# ECG_PressureSensor.net
KiCad netlist of a schematic drawn in Altium Designer
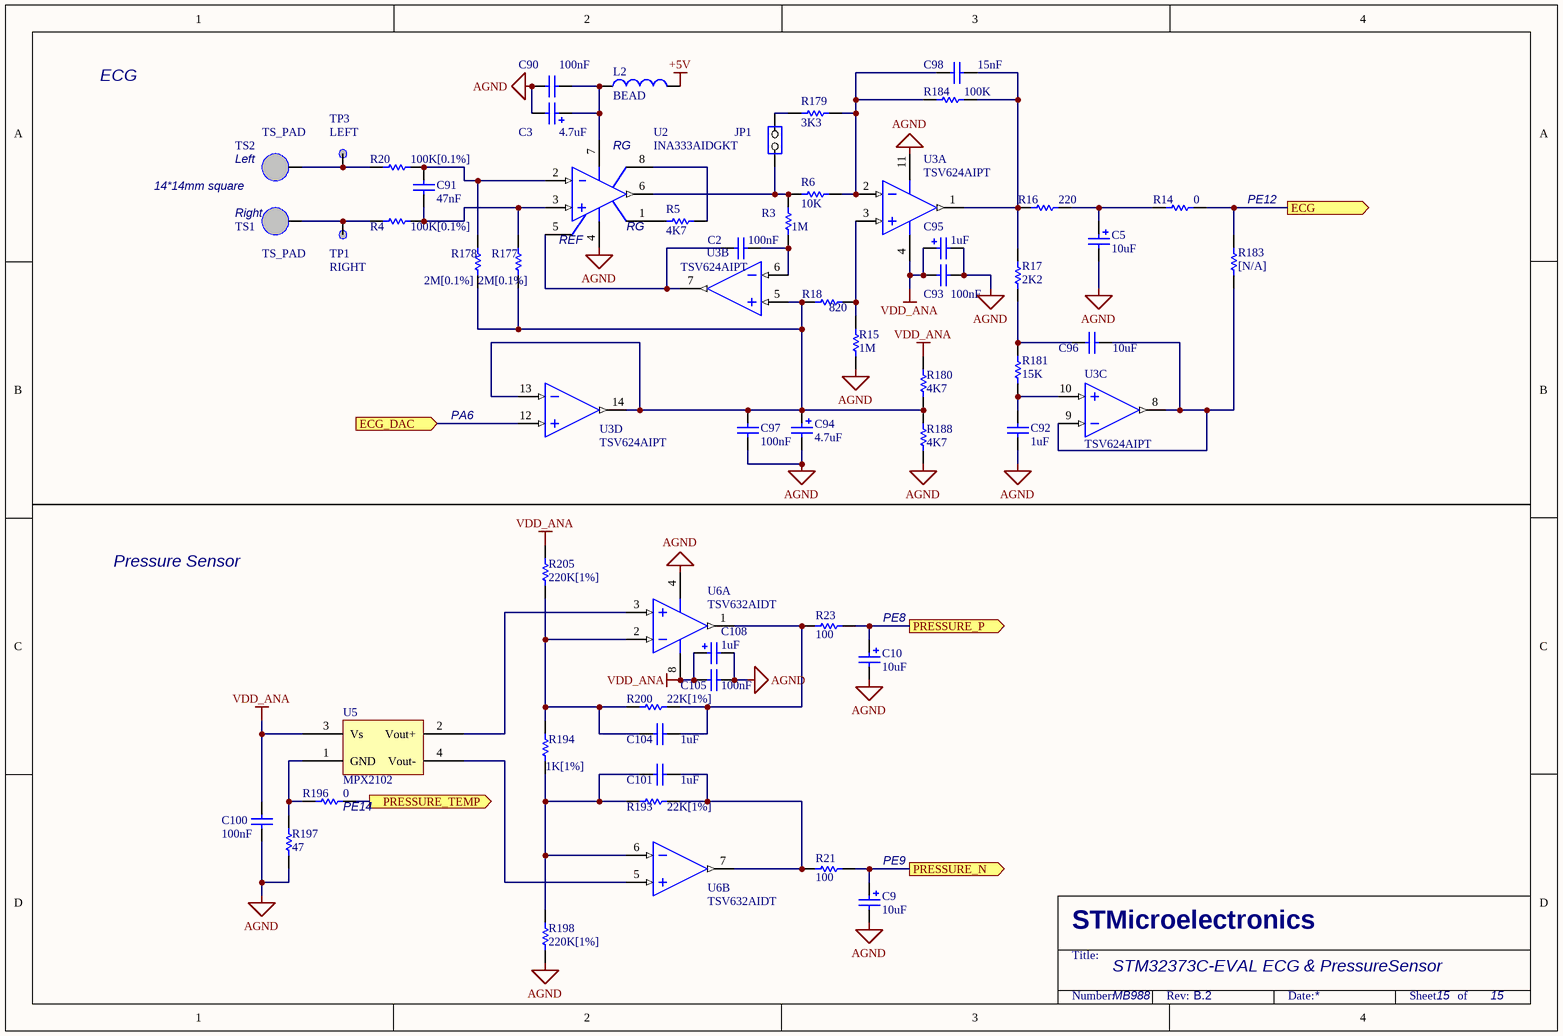
[diagram p0: ECG&PressureSensor.SchDoc]

(export (version "E")
  (design (tool "Eeschema 10.0.6"))
  (components
    (comp (ref "C2")
      (value "100nF")
      (footprint "0603C")
      (description "Capacitor")
      (fields (field (name "PUBLISHER") "Altium Limited"))
      (libsource (lib "Miscellaneous Devices") (part "CAP"))
    )
    (comp (ref "C3")
      (value "4.7uF")
      (footprint "TAN-A")
      (description "Polarized Capacitor (Radial)")
      (fields (field (name "PUBLISHER") "Altium Limited"))
      (libsource (lib "*") (part "Cap Pol1"))
    )
    (comp (ref "C5")
      (value "10uF")
      (footprint "TAN-A")
      (description "Polarized Capacitor (Radial)")
      (fields (field (name "PUBLISHER") "Altium Limited"))
      (libsource (lib "Miscellaneous Devices") (part "Cap Pol1"))
    )
    (comp (ref "C9")
      (value "10uF")
      (footprint "TAN-A")
      (description "Polarized Capacitor (Radial)")
      (fields (field (name "PUBLISHER") "Altium Limited"))
      (libsource (lib "Miscellaneous Devices") (part "Cap Pol1"))
    )
    (comp (ref "C10")
      (value "10uF")
      (footprint "TAN-A")
      (description "Polarized Capacitor (Radial)")
      (fields (field (name "PUBLISHER") "Altium Limited"))
      (libsource (lib "Miscellaneous Devices") (part "Cap Pol1"))
    )
    (comp (ref "C90")
      (value "100nF")
      (footprint "0603C")
      (description "Capacitor")
      (fields (field (name "PUBLISHER") "Altium Limited"))
      (libsource (lib "Miscellaneous Devices") (part "CAP"))
    )
    (comp (ref "C91")
      (value "47nF")
      (footprint "0603C")
      (description "Capacitor")
      (fields (field (name "PUBLISHER") "Altium Limited"))
      (libsource (lib "Miscellaneous Devices") (part "CAP"))
    )
    (comp (ref "C92")
      (value "1uF")
      (footprint "0603C")
      (description "Capacitor")
      (fields (field (name "PUBLISHER") "Altium Limited"))
      (libsource (lib "Miscellaneous Devices") (part "CAP"))
    )
    (comp (ref "C93")
      (value "100nF")
      (footprint "0603C")
      (description "Capacitor")
      (fields (field (name "PUBLISHER") "Altium Limited"))
      (libsource (lib "Miscellaneous Devices") (part "CAP"))
    )
    (comp (ref "C94")
      (value "4.7uF")
      (footprint "TAN-A")
      (description "Polarized Capacitor (Radial)")
      (fields (field (name "PUBLISHER") "Altium Limited"))
      (libsource (lib "*") (part "Cap Pol1"))
    )
    (comp (ref "C95")
      (value "1uF")
      (footprint "TAN-A")
      (description "Polarized Capacitor (Radial)")
      (fields (field (name "PUBLISHER") "Altium Limited"))
      (libsource (lib "Miscellaneous Devices") (part "Cap Pol1"))
    )
    (comp (ref "C96")
      (value "10uF")
      (footprint "0805C")
      (description "Capacitor")
      (fields (field (name "PUBLISHER") "Altium Limited"))
      (libsource (lib "Miscellaneous Devices") (part "CAP"))
    )
    (comp (ref "C97")
      (value "100nF")
      (footprint "0603C")
      (description "Capacitor")
      (fields (field (name "PUBLISHER") "Altium Limited"))
      (libsource (lib "Miscellaneous Devices") (part "CAP"))
    )
    (comp (ref "C98")
      (value "15nF")
      (footprint "0603C")
      (description "Capacitor")
      (fields (field (name "PUBLISHER") "Altium Limited"))
      (libsource (lib "Miscellaneous Devices") (part "CAP"))
    )
    (comp (ref "C100")
      (value "100nF")
      (footprint "0603C")
      (description "Capacitor")
      (fields (field (name "PUBLISHER") "Altium Limited"))
      (libsource (lib "Miscellaneous Devices") (part "CAP"))
    )
    (comp (ref "C101")
      (value "1uF")
      (footprint "0603C")
      (description "Capacitor")
      (fields (field (name "PUBLISHER") "Altium Limited"))
      (libsource (lib "Miscellaneous Devices") (part "CAP"))
    )
    (comp (ref "C104")
      (value "1uF")
      (footprint "0603C")
      (description "Capacitor")
      (fields (field (name "PUBLISHER") "Altium Limited"))
      (libsource (lib "Miscellaneous Devices") (part "CAP"))
    )
    (comp (ref "C105")
      (value "100nF")
      (footprint "0603C")
      (description "Capacitor")
      (fields (field (name "PUBLISHER") "Altium Limited"))
      (libsource (lib "Miscellaneous Devices") (part "CAP"))
    )
    (comp (ref "C108")
      (value "1uF")
      (footprint "TAN-A")
      (description "Polarized Capacitor (Radial)")
      (fields (field (name "PUBLISHER") "Altium Limited"))
      (libsource (lib "Miscellaneous Devices") (part "Cap Pol1"))
    )
    (comp (ref "JP1") (value "~") (footprint "SIP2") (libsource (lib "*") (part "JP2")))
    (comp (ref "L2")
      (value "BEAD")
      (footprint "0603L")
      (description "Inductor")
      (fields (field (name "PUBLISHER") "Altium Limited"))
      (libsource (lib "Miscellaneous Devices") (part "Inductor"))
    )
    (comp (ref "R3")
      (value "1M")
      (footprint "0603R")
      (description "Resistor")
      (fields (field (name "PUBLISHER") "Altium Limited"))
      (libsource (lib "Miscellaneous Devices") (part "Res1"))
    )
    (comp (ref "R4")
      (value "100K[0.1%]")
      (footprint "0603R")
      (description "Resistor")
      (fields (field (name "PUBLISHER") "Altium Limited"))
      (libsource (lib "Miscellaneous Devices") (part "Res1"))
    )
    (comp (ref "R5")
      (value "4K7")
      (footprint "0603R")
      (description "Resistor")
      (fields (field (name "PUBLISHER") "Altium Limited"))
      (libsource (lib "Miscellaneous Devices") (part "Res1"))
    )
    (comp (ref "R6")
      (value "10K")
      (footprint "0603R")
      (description "Resistor")
      (fields (field (name "PUBLISHER") "Altium Limited"))
      (libsource (lib "Miscellaneous Devices") (part "res1"))
    )
    (comp (ref "R14")
      (value "0")
      (footprint "0603R")
      (description "Resistor")
      (fields (field (name "PUBLISHER") "Altium Limited"))
      (libsource (lib "Miscellaneous Devices") (part "Res1"))
    )
    (comp (ref "R15")
      (value "1M")
      (footprint "0603R")
      (description "Resistor")
      (fields (field (name "PUBLISHER") "Altium Limited"))
      (libsource (lib "Miscellaneous Devices") (part "Res1"))
    )
    (comp (ref "R16")
      (value "220")
      (footprint "0603R")
      (description "Resistor")
      (fields (field (name "PUBLISHER") "Altium Limited"))
      (libsource (lib "Miscellaneous Devices") (part "Res1"))
    )
    (comp (ref "R17")
      (value "2K2")
      (description "Resistor")
      (fields (field (name "PUBLISHER") "Altium Limited"))
      (libsource (lib "Miscellaneous Devices") (part "Res1"))
    )
    (comp (ref "R18")
      (value "820")
      (footprint "0603R")
      (description "Resistor")
      (fields (field (name "PUBLISHER") "Altium Limited"))
      (libsource (lib "Miscellaneous Devices") (part "Res1"))
    )
    (comp (ref "R20")
      (value "100K[0.1%]")
      (footprint "0603R")
      (description "Resistor")
      (fields (field (name "PUBLISHER") "Altium Limited"))
      (libsource (lib "Miscellaneous Devices") (part "Res1"))
    )
    (comp (ref "R21")
      (value "100")
      (footprint "0603R")
      (description "Resistor")
      (fields (field (name "PUBLISHER") "Altium Limited"))
      (libsource (lib "Miscellaneous Devices") (part "Res1"))
    )
    (comp (ref "R23")
      (value "100")
      (footprint "0603R")
      (description "Resistor")
      (fields (field (name "PUBLISHER") "Altium Limited"))
      (libsource (lib "Miscellaneous Devices") (part "Res1"))
    )
    (comp (ref "R177")
      (value "2M[0.1%]")
      (footprint "0603R")
      (description "Resistor")
      (fields (field (name "PUBLISHER") "Altium Limited"))
      (libsource (lib "Miscellaneous Devices") (part "Res1"))
    )
    (comp (ref "R178")
      (value "2M[0.1%]")
      (footprint "0603R")
      (description "Resistor")
      (fields (field (name "PUBLISHER") "Altium Limited"))
      (libsource (lib "Miscellaneous Devices") (part "Res1"))
    )
    (comp (ref "R179")
      (value "3K3")
      (description "Resistor")
      (fields (field (name "PUBLISHER") "Altium Limited"))
      (libsource (lib "Miscellaneous Devices") (part "Res1"))
    )
    (comp (ref "R180")
      (value "4K7")
      (footprint "0603R")
      (description "Resistor")
      (fields (field (name "PUBLISHER") "Altium Limited"))
      (libsource (lib "Miscellaneous Devices") (part "Res1"))
    )
    (comp (ref "R181")
      (value "15K")
      (footprint "0603R")
      (description "Resistor")
      (fields (field (name "PUBLISHER") "Altium Limited"))
      (libsource (lib "Miscellaneous Devices") (part "Res1"))
    )
    (comp (ref "R183")
      (value "[N/A]")
      (footprint "0603R")
      (description "Resistor")
      (fields (field (name "PUBLISHER") "Altium Limited"))
      (libsource (lib "Miscellaneous Devices") (part "Res1"))
    )
    (comp (ref "R184")
      (value "100K")
      (footprint "0603R")
      (description "Resistor")
      (fields (field (name "PUBLISHER") "Altium Limited"))
      (libsource (lib "Miscellaneous Devices") (part "Res1"))
    )
    (comp (ref "R188")
      (value "4K7")
      (footprint "0603R")
      (description "Resistor")
      (fields (field (name "PUBLISHER") "Altium Limited"))
      (libsource (lib "Miscellaneous Devices") (part "Res1"))
    )
    (comp (ref "R193")
      (value "22K[1%]")
      (footprint "0603R")
      (description "Resistor")
      (fields (field (name "PUBLISHER") "Altium Limited"))
      (libsource (lib "Miscellaneous Devices") (part "Res1"))
    )
    (comp (ref "R194")
      (value "1K[1%]")
      (footprint "0603R")
      (description "Resistor")
      (fields (field (name "PUBLISHER") "Altium Limited"))
      (libsource (lib "Miscellaneous Devices") (part "Res1"))
    )
    (comp (ref "R196")
      (value "0")
      (footprint "0603R")
      (description "Resistor")
      (fields (field (name "PUBLISHER") "Altium Limited"))
      (libsource (lib "Miscellaneous Devices") (part "Res1"))
    )
    (comp (ref "R197")
      (value "47")
      (footprint "0603R")
      (description "Resistor")
      (fields (field (name "PUBLISHER") "Altium Limited"))
      (libsource (lib "Miscellaneous Devices") (part "Res1"))
    )
    (comp (ref "R198")
      (value "220K[1%]")
      (footprint "0603R")
      (description "Resistor")
      (fields (field (name "PUBLISHER") "Altium Limited"))
      (libsource (lib "Miscellaneous Devices") (part "Res1"))
    )
    (comp (ref "R200")
      (value "22K[1%]")
      (footprint "0603R")
      (description "Resistor")
      (fields (field (name "PUBLISHER") "Altium Limited"))
      (libsource (lib "Miscellaneous Devices") (part "Res1"))
    )
    (comp (ref "R205")
      (value "220K[1%]")
      (footprint "0603R")
      (description "Resistor")
      (fields (field (name "PUBLISHER") "Altium Limited"))
      (libsource (lib "Miscellaneous Devices") (part "Res1"))
    )
    (comp (ref "TP1") (value "RIGHT") (footprint "TP") (libsource (lib "*") (part "TP")))
    (comp (ref "TP3") (value "LEFT") (footprint "TP") (libsource (lib "*") (part "TP")))
    (comp (ref "TS1") (value "TS_PAD") (footprint "TS_PAD") (libsource (lib "MB819") (part "TS_PAD")))
    (comp (ref "TS2") (value "TS_PAD") (footprint "TS_PAD") (libsource (lib "MB819") (part "TS_PAD")))
    (comp (ref "U2") (value "INA333AIDGKT") (footprint "MSOP8") (libsource (lib "MB988") (part "INA333")))
    (comp (ref "U3") (value "TSV624AIPT") (footprint "TSSOP14") (libsource (lib "MB988") (part "TSV624A")))
    (comp (ref "U5") (value "MPX2102") (footprint "MPAK") (libsource (lib "MB988") (part "MPX2102")))
    (comp (ref "U6") (value "TSV632AIDT") (footprint "SO8") (libsource (lib "MB988") (part "TSV632AIDT")))
  )
  (nets
    (net (code "1") (name "+5V") (class "Default")
      (node (ref "L2") (pin "2") (pinfunction "2_2") (pintype "passive"))
    )
    (net (code "2") (name "/ECG") (class "Default")
      (node (ref "R14") (pin "1") (pinfunction "1_1") (pintype "passive"))
      (node (ref "R183") (pin "1") (pinfunction "1_1") (pintype "passive"))
    )
    (net (code "3") (name "/ECG_DAC") (class "Default")
      (node (ref "U3") (pin "12") (pinfunction "IN+_12") (pintype "input"))
    )
    (net (code "4") (name "/PRESSURE_N") (class "Default")
      (node (ref "C9") (pin "1") (pinfunction "1_1") (pintype "passive"))
      (node (ref "R21") (pin "1") (pinfunction "1_1") (pintype "passive"))
    )
    (net (code "5") (name "/PRESSURE_P") (class "Default")
      (node (ref "C10") (pin "1") (pinfunction "1_1") (pintype "passive"))
      (node (ref "R23") (pin "1") (pinfunction "1_1") (pintype "passive"))
    )
    (net (code "6") (name "/PRESSURE_TEMP") (class "Default")
      (node (ref "R196") (pin "1") (pinfunction "1_1") (pintype "passive"))
    )
    (net (code "7") (name "AGND") (class "Default")
      (node (ref "C10") (pin "2") (pinfunction "2_2") (pintype "passive"))
      (node (ref "C100") (pin "1") (pinfunction "1_1") (pintype "passive"))
      (node (ref "C105") (pin "1") (pinfunction "1_1") (pintype "passive"))
      (node (ref "C108") (pin "2") (pinfunction "2_2") (pintype "passive"))
      (node (ref "C3") (pin "2") (pinfunction "2_2") (pintype "passive"))
      (node (ref "C5") (pin "2") (pinfunction "2_2") (pintype "passive"))
      (node (ref "C9") (pin "2") (pinfunction "2_2") (pintype "passive"))
      (node (ref "C90") (pin "1") (pinfunction "1_1") (pintype "passive"))
      (node (ref "C92") (pin "1") (pinfunction "1_1") (pintype "passive"))
      (node (ref "C93") (pin "1") (pinfunction "1_1") (pintype "passive"))
      (node (ref "C94") (pin "2") (pinfunction "2_2") (pintype "passive"))
      (node (ref "C95") (pin "2") (pinfunction "2_2") (pintype "passive"))
      (node (ref "C97") (pin "1") (pinfunction "1_1") (pintype "passive"))
      (node (ref "R15") (pin "1") (pinfunction "1_1") (pintype "passive"))
      (node (ref "R188") (pin "1") (pinfunction "1_1") (pintype "passive"))
      (node (ref "R197") (pin "1") (pinfunction "1_1") (pintype "passive"))
      (node (ref "R198") (pin "2") (pinfunction "2_2") (pintype "passive"))
      (node (ref "U2") (pin "4") (pinfunction "V-_4") (pintype "power_in"))
      (node (ref "U3") (pin "11") (pinfunction "V+_11") (pintype "power_in"))
      (node (ref "U6") (pin "4") (pinfunction "V-_4") (pintype "power_in"))
    )
    (net (code "8") (name "Net-(C5-Pad1)") (class "Default")
      (node (ref "C5") (pin "1") (pinfunction "1_1") (pintype "passive"))
      (node (ref "R14") (pin "2") (pinfunction "2_2") (pintype "passive"))
      (node (ref "R16") (pin "2") (pinfunction "2_2") (pintype "passive"))
    )
    (net (code "9") (name "Net-(C96-Pad1)") (class "Default")
      (node (ref "C96") (pin "1") (pinfunction "1_1") (pintype "passive"))
      (node (ref "R17") (pin "2") (pinfunction "2_2") (pintype "passive"))
      (node (ref "R181") (pin "2") (pinfunction "2_2") (pintype "passive"))
    )
    (net (code "10") (name "Net-(JP1-COMMON)") (class "Default")
      (node (ref "JP1") (pin "1") (pinfunction "COMMON_1") (pintype "passive"))
      (node (ref "R179") (pin "2") (pinfunction "2_2") (pintype "passive"))
    )
    (net (code "11") (name "Net-(JP1-NO)") (class "Default")
      (node (ref "JP1") (pin "2") (pinfunction "NO_2") (pintype "passive"))
      (node (ref "R3") (pin "2") (pinfunction "2_2") (pintype "passive"))
      (node (ref "R6") (pin "1") (pinfunction "1_1") (pintype "passive"))
      (node (ref "U2") (pin "6") (pinfunction "OUT_6") (pintype "output"))
    )
    (net (code "12") (name "Net-(R4-Pad1)") (class "Default")
      (node (ref "R4") (pin "1") (pinfunction "1_1") (pintype "passive"))
      (node (ref "TP1") (pin "1") (pinfunction "1_1") (pintype "passive"))
      (node (ref "TS1") (pin "1") (pinfunction "1_1") (pintype "passive"))
    )
    (net (code "13") (name "Net-(R5-Pad1)") (class "Default")
      (node (ref "R5") (pin "1") (pinfunction "1_1") (pintype "passive"))
      (node (ref "U2") (pin "8") (pinfunction "RG_8") (pintype "power_in"))
    )
    (net (code "14") (name "Net-(R5-Pad2)") (class "Default")
      (node (ref "R5") (pin "2") (pinfunction "2_2") (pintype "passive"))
      (node (ref "U2") (pin "1") (pinfunction "RG_1") (pintype "power_in"))
    )
    (net (code "15") (name "Net-(R20-Pad1)") (class "Default")
      (node (ref "R20") (pin "1") (pinfunction "1_1") (pintype "passive"))
      (node (ref "TP3") (pin "1") (pinfunction "1_1") (pintype "passive"))
      (node (ref "TS2") (pin "1") (pinfunction "1_1") (pintype "passive"))
    )
    (net (code "16") (name "Net-(U2-IN+)") (class "Default")
      (node (ref "C91") (pin "1") (pinfunction "1_1") (pintype "passive"))
      (node (ref "R177") (pin "2") (pinfunction "2_2") (pintype "passive"))
      (node (ref "R4") (pin "2") (pinfunction "2_2") (pintype "passive"))
      (node (ref "U2") (pin "3") (pinfunction "IN+_3") (pintype "input"))
    )
    (net (code "17") (name "Net-(U2-IN-)") (class "Default")
      (node (ref "C91") (pin "2") (pinfunction "2_2") (pintype "passive"))
      (node (ref "R178") (pin "2") (pinfunction "2_2") (pintype "passive"))
      (node (ref "R20") (pin "2") (pinfunction "2_2") (pintype "passive"))
      (node (ref "U2") (pin "2") (pinfunction "IN-_2") (pintype "input"))
    )
    (net (code "18") (name "Net-(U2-REF)") (class "Default")
      (node (ref "C2") (pin "1") (pinfunction "1_1") (pintype "passive"))
      (node (ref "U2") (pin "5") (pinfunction "REF_5") (pintype "power_in"))
      (node (ref "U3") (pin "7") (pinfunction "OUT_7") (pintype "output"))
    )
    (net (code "19") (name "Net-(U2-V+)") (class "Default")
      (node (ref "C3") (pin "1") (pinfunction "1_1") (pintype "passive"))
      (node (ref "C90") (pin "2") (pinfunction "2_2") (pintype "passive"))
      (node (ref "L2") (pin "1") (pinfunction "1_1") (pintype "passive"))
      (node (ref "U2") (pin "7") (pinfunction "V+_7") (pintype "power_in"))
    )
    (net (code "20") (name "Net-(U3A-IN+)") (class "Default")
      (node (ref "R15") (pin "2") (pinfunction "2_2") (pintype "passive"))
      (node (ref "R18") (pin "2") (pinfunction "2_2") (pintype "passive"))
      (node (ref "U3") (pin "3") (pinfunction "IN+_3") (pintype "input"))
    )
    (net (code "21") (name "Net-(U3A-IN-)") (class "Default")
      (node (ref "C98") (pin "2") (pinfunction "2_2") (pintype "passive"))
      (node (ref "R179") (pin "1") (pinfunction "1_1") (pintype "passive"))
      (node (ref "R184") (pin "1") (pinfunction "1_1") (pintype "passive"))
      (node (ref "R6") (pin "2") (pinfunction "2_2") (pintype "passive"))
      (node (ref "U3") (pin "2") (pinfunction "IN-_2") (pintype "input"))
    )
    (net (code "22") (name "Net-(U3A-OUT)") (class "Default")
      (node (ref "C98") (pin "1") (pinfunction "1_1") (pintype "passive"))
      (node (ref "R16") (pin "1") (pinfunction "1_1") (pintype "passive"))
      (node (ref "R17") (pin "1") (pinfunction "1_1") (pintype "passive"))
      (node (ref "R184") (pin "2") (pinfunction "2_2") (pintype "passive"))
      (node (ref "U3") (pin "1") (pinfunction "OUT_1") (pintype "output"))
    )
    (net (code "23") (name "Net-(U3B-IN+)") (class "Default")
      (node (ref "C94") (pin "1") (pinfunction "1_1") (pintype "passive"))
      (node (ref "C97") (pin "2") (pinfunction "2_2") (pintype "passive"))
      (node (ref "R177") (pin "1") (pinfunction "1_1") (pintype "passive"))
      (node (ref "R178") (pin "1") (pinfunction "1_1") (pintype "passive"))
      (node (ref "R18") (pin "1") (pinfunction "1_1") (pintype "passive"))
      (node (ref "R180") (pin "1") (pinfunction "1_1") (pintype "passive"))
      (node (ref "R188") (pin "2") (pinfunction "2_2") (pintype "passive"))
      (node (ref "U3") (pin "13") (pinfunction "IN-_13") (pintype "input"))
      (node (ref "U3") (pin "14") (pinfunction "OUT_14") (pintype "output"))
      (node (ref "U3") (pin "5") (pinfunction "IN+_5") (pintype "input"))
    )
    (net (code "24") (name "Net-(U3B-IN-)") (class "Default")
      (node (ref "C2") (pin "2") (pinfunction "2_2") (pintype "passive"))
      (node (ref "R3") (pin "1") (pinfunction "1_1") (pintype "passive"))
      (node (ref "U3") (pin "6") (pinfunction "IN-_6") (pintype "input"))
    )
    (net (code "25") (name "Net-(U3C-IN+)") (class "Default")
      (node (ref "C92") (pin "2") (pinfunction "2_2") (pintype "passive"))
      (node (ref "R181") (pin "1") (pinfunction "1_1") (pintype "passive"))
      (node (ref "U3") (pin "10") (pinfunction "IN+_10") (pintype "input"))
    )
    (net (code "26") (name "Net-(U3C-IN-)") (class "Default")
      (node (ref "C96") (pin "2") (pinfunction "2_2") (pintype "passive"))
      (node (ref "R183") (pin "2") (pinfunction "2_2") (pintype "passive"))
      (node (ref "U3") (pin "8") (pinfunction "OUT_8") (pintype "output"))
      (node (ref "U3") (pin "9") (pinfunction "IN-_9") (pintype "input"))
    )
    (net (code "27") (name "Net-(U5-GND)") (class "Default")
      (node (ref "R196") (pin "2") (pinfunction "2_2") (pintype "passive"))
      (node (ref "R197") (pin "2") (pinfunction "2_2") (pintype "passive"))
      (node (ref "U5") (pin "1") (pinfunction "GND_1") (pintype "passive"))
    )
    (net (code "28") (name "Net-(U5-Vout+)") (class "Default")
      (node (ref "U5") (pin "2") (pinfunction "Vout+_2") (pintype "passive"))
      (node (ref "U6") (pin "3") (pinfunction "IN+_3") (pintype "input"))
    )
    (net (code "29") (name "Net-(U5-Vout-)") (class "Default")
      (node (ref "U5") (pin "4") (pinfunction "Vout-_4") (pintype "passive"))
      (node (ref "U6") (pin "5") (pinfunction "IN+_5") (pintype "input"))
    )
    (net (code "30") (name "Net-(U6A-IN-)") (class "Default")
      (node (ref "C104") (pin "1") (pinfunction "1_1") (pintype "passive"))
      (node (ref "R194") (pin "2") (pinfunction "2_2") (pintype "passive"))
      (node (ref "R200") (pin "1") (pinfunction "1_1") (pintype "passive"))
      (node (ref "R205") (pin "2") (pinfunction "2_2") (pintype "passive"))
      (node (ref "U6") (pin "2") (pinfunction "IN-_2") (pintype "input"))
    )
    (net (code "31") (name "Net-(U6A-OUT)") (class "Default")
      (node (ref "C104") (pin "2") (pinfunction "2_2") (pintype "passive"))
      (node (ref "R200") (pin "2") (pinfunction "2_2") (pintype "passive"))
      (node (ref "R23") (pin "2") (pinfunction "2_2") (pintype "passive"))
      (node (ref "U6") (pin "1") (pinfunction "OUT_1") (pintype "output"))
    )
    (net (code "32") (name "Net-(U6B-IN-)") (class "Default")
      (node (ref "C101") (pin "1") (pinfunction "1_1") (pintype "passive"))
      (node (ref "R193") (pin "1") (pinfunction "1_1") (pintype "passive"))
      (node (ref "R194") (pin "1") (pinfunction "1_1") (pintype "passive"))
      (node (ref "R198") (pin "1") (pinfunction "1_1") (pintype "passive"))
      (node (ref "U6") (pin "6") (pinfunction "IN-_6") (pintype "input"))
    )
    (net (code "33") (name "Net-(U6B-OUT)") (class "Default")
      (node (ref "C101") (pin "2") (pinfunction "2_2") (pintype "passive"))
      (node (ref "R193") (pin "2") (pinfunction "2_2") (pintype "passive"))
      (node (ref "R21") (pin "2") (pinfunction "2_2") (pintype "passive"))
      (node (ref "U6") (pin "7") (pinfunction "OUT_7") (pintype "output"))
    )
    (net (code "34") (name "VDD_ANA") (class "Default")
      (node (ref "C100") (pin "2") (pinfunction "2_2") (pintype "passive"))
      (node (ref "C105") (pin "2") (pinfunction "2_2") (pintype "passive"))
      (node (ref "C108") (pin "1") (pinfunction "1_1") (pintype "passive"))
      (node (ref "C93") (pin "2") (pinfunction "2_2") (pintype "passive"))
      (node (ref "C95") (pin "1") (pinfunction "1_1") (pintype "passive"))
      (node (ref "R180") (pin "2") (pinfunction "2_2") (pintype "passive"))
      (node (ref "R205") (pin "1") (pinfunction "1_1") (pintype "passive"))
      (node (ref "U3") (pin "4") (pinfunction "V-_4") (pintype "power_in"))
      (node (ref "U5") (pin "3") (pinfunction "Vs_3") (pintype "passive"))
      (node (ref "U6") (pin "8") (pinfunction "V+_8") (pintype "power_in"))
    )
  )
)
